# STEP6.net
KiCad netlist of a schematic drawn in EAGLE
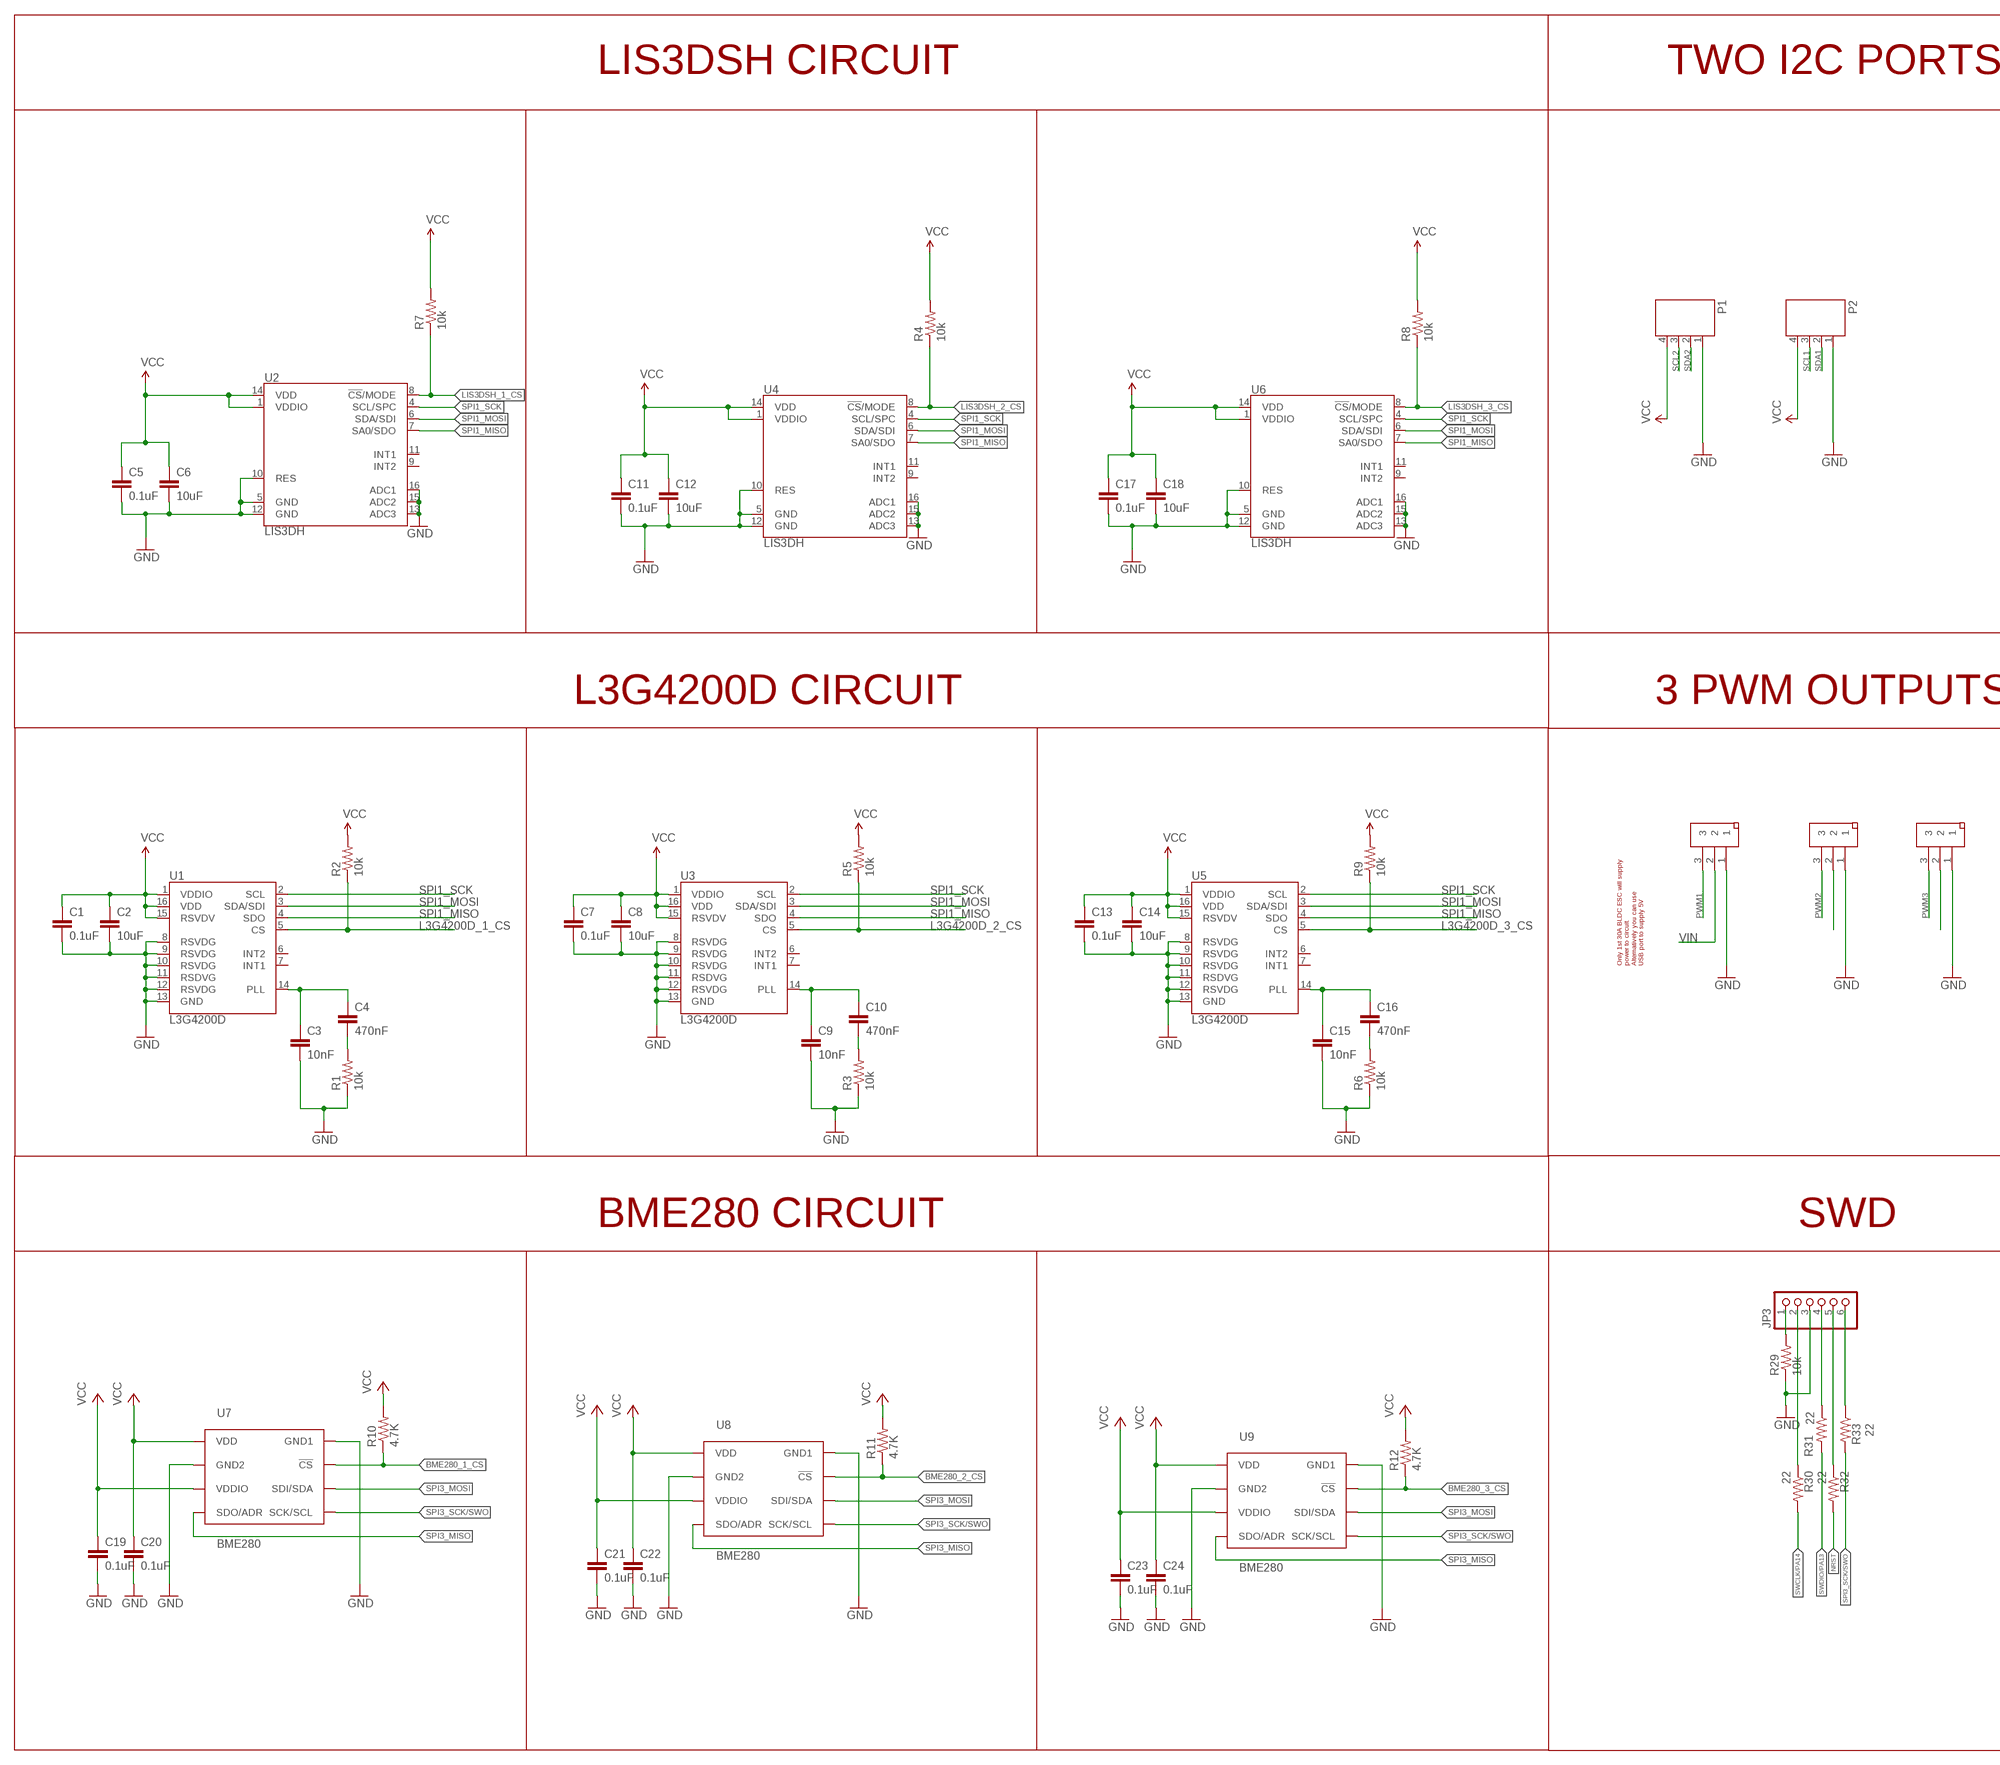
[diagram p0: schematic, sheet 1, part 1 of 2]
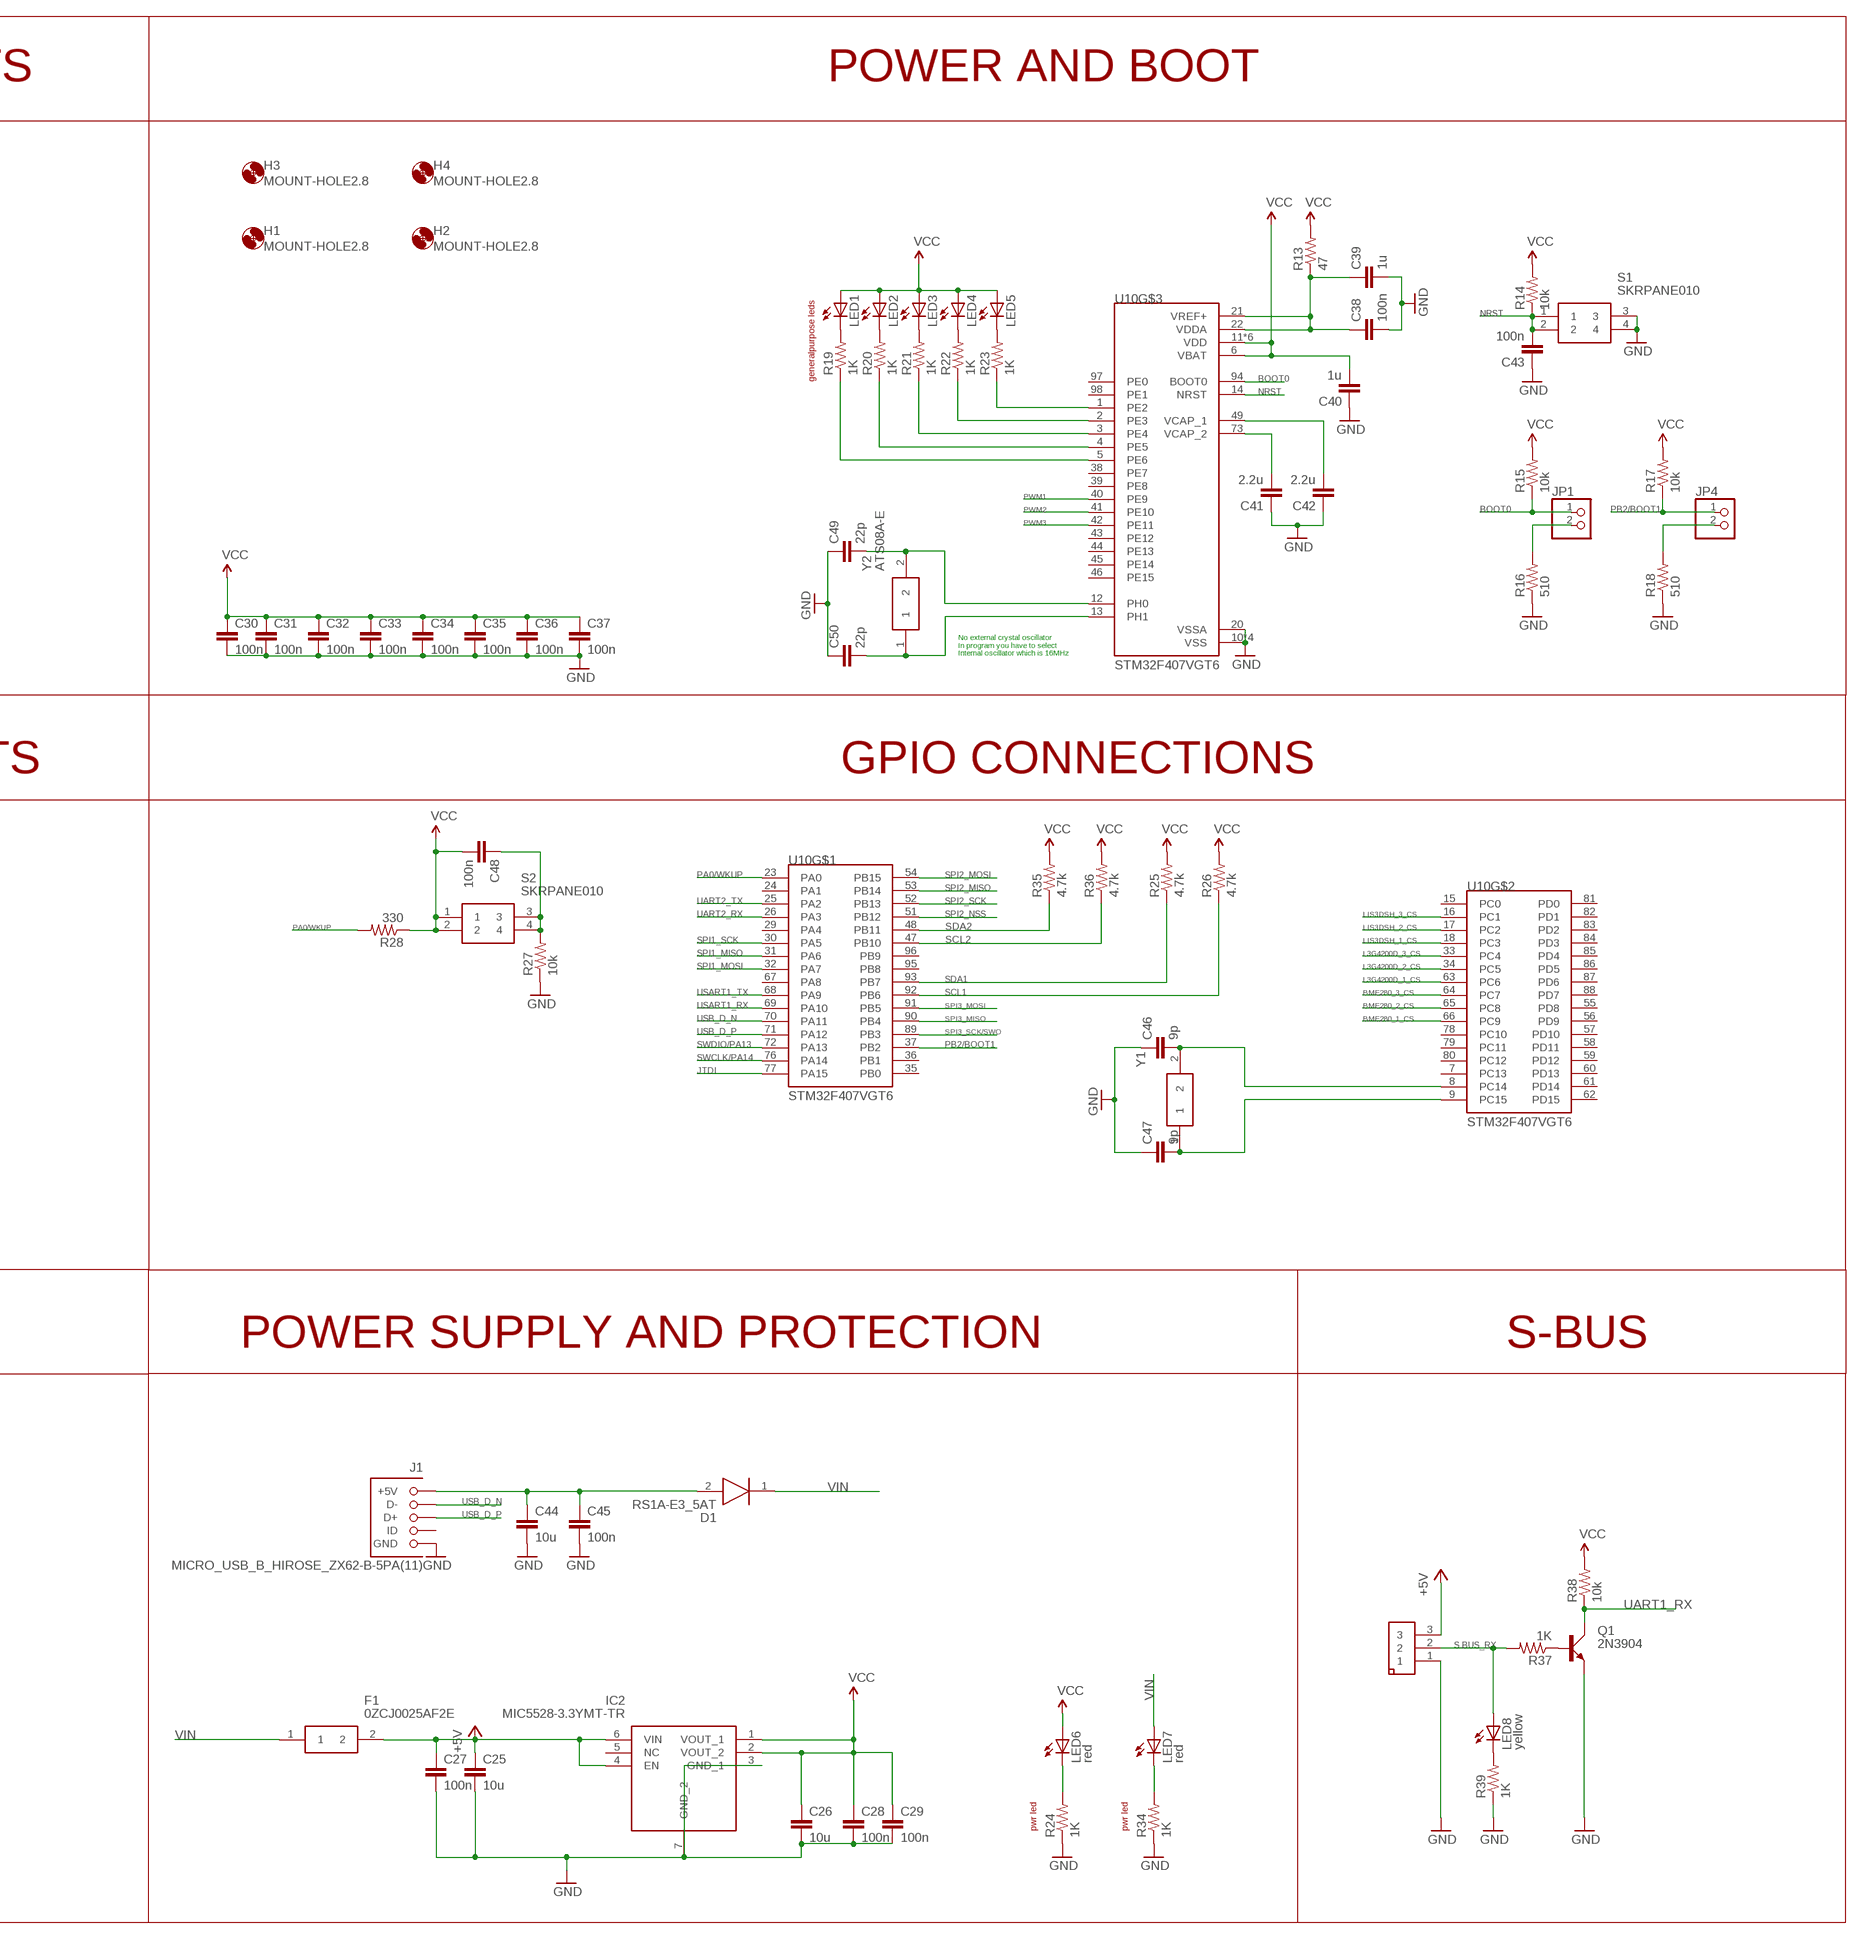
[diagram p1: schematic, sheet 1, part 2 of 2]

(export (version "E")
  (design (tool "Eeschema 10.0.6"))
  (components
    (comp (ref "C1")
      (value "0.1uF")
      (footprint "eagle-import:0402-CAP")
      (libsource (lib "eagle-import") (part "CAP0402-CAP"))
    )
    (comp (ref "C2")
      (value "10uF")
      (footprint "eagle-import:1206")
      (libsource (lib "eagle-import") (part "CAP1206"))
    )
    (comp (ref "C3")
      (value "10nF")
      (footprint "eagle-import:0402-CAP")
      (libsource (lib "eagle-import") (part "CAP0402-CAP"))
    )
    (comp (ref "C4")
      (value "470nF")
      (footprint "eagle-import:0402-CAP")
      (libsource (lib "eagle-import") (part "CAP0402-CAP"))
    )
    (comp (ref "C5")
      (value "0.1uF")
      (footprint "eagle-import:0402")
      (libsource (lib "eagle-import") (part "0.1UF-0402-16V-10%"))
    )
    (comp (ref "C6")
      (value "10uF")
      (footprint "eagle-import:0603")
      (libsource (lib "eagle-import") (part "10UF-0603-6.3V-20%"))
    )
    (comp (ref "C7")
      (value "0.1uF")
      (footprint "eagle-import:0402-CAP")
      (libsource (lib "eagle-import") (part "CAP0402-CAP"))
    )
    (comp (ref "C8")
      (value "10uF")
      (footprint "eagle-import:1206")
      (libsource (lib "eagle-import") (part "CAP1206"))
    )
    (comp (ref "C9")
      (value "10nF")
      (footprint "eagle-import:0402-CAP")
      (libsource (lib "eagle-import") (part "CAP0402-CAP"))
    )
    (comp (ref "C10")
      (value "470nF")
      (footprint "eagle-import:0402-CAP")
      (libsource (lib "eagle-import") (part "CAP0402-CAP"))
    )
    (comp (ref "C11")
      (value "0.1uF")
      (footprint "eagle-import:0402")
      (libsource (lib "eagle-import") (part "0.1UF-0402-16V-10%"))
    )
    (comp (ref "C12")
      (value "10uF")
      (footprint "eagle-import:0603")
      (libsource (lib "eagle-import") (part "10UF-0603-6.3V-20%"))
    )
    (comp (ref "C13")
      (value "0.1uF")
      (footprint "eagle-import:0402-CAP")
      (libsource (lib "eagle-import") (part "CAP0402-CAP"))
    )
    (comp (ref "C14")
      (value "10uF")
      (footprint "eagle-import:1206")
      (libsource (lib "eagle-import") (part "CAP1206"))
    )
    (comp (ref "C15")
      (value "10nF")
      (footprint "eagle-import:0402-CAP")
      (libsource (lib "eagle-import") (part "CAP0402-CAP"))
    )
    (comp (ref "C16")
      (value "470nF")
      (footprint "eagle-import:0402-CAP")
      (libsource (lib "eagle-import") (part "CAP0402-CAP"))
    )
    (comp (ref "C17")
      (value "0.1uF")
      (footprint "eagle-import:0402")
      (libsource (lib "eagle-import") (part "0.1UF-0402-16V-10%"))
    )
    (comp (ref "C18")
      (value "10uF")
      (footprint "eagle-import:0603")
      (libsource (lib "eagle-import") (part "10UF-0603-6.3V-20%"))
    )
    (comp (ref "C19")
      (value "0.1uF")
      (footprint "eagle-import:0603-CAP")
      (libsource (lib "eagle-import") (part "0.1UF-25V-5%(0603)"))
    )
    (comp (ref "C20")
      (value "0.1uF")
      (footprint "eagle-import:0603-CAP")
      (libsource (lib "eagle-import") (part "0.1UF-25V-5%(0603)"))
    )
    (comp (ref "C21")
      (value "0.1uF")
      (footprint "eagle-import:0603-CAP")
      (libsource (lib "eagle-import") (part "0.1UF-25V-5%(0603)"))
    )
    (comp (ref "C22")
      (value "0.1uF")
      (footprint "eagle-import:0603-CAP")
      (libsource (lib "eagle-import") (part "0.1UF-25V-5%(0603)"))
    )
    (comp (ref "C23")
      (value "0.1uF")
      (footprint "eagle-import:0603-CAP")
      (libsource (lib "eagle-import") (part "0.1UF-25V-5%(0603)"))
    )
    (comp (ref "C24")
      (value "0.1uF")
      (footprint "eagle-import:0603-CAP")
      (libsource (lib "eagle-import") (part "0.1UF-25V-5%(0603)"))
    )
    (comp (ref "C25")
      (value "10u")
      (footprint "eagle-import:C0805")
      (libsource (lib "eagle-import") (part "C-EUC0805"))
    )
    (comp (ref "C26")
      (value "10u")
      (footprint "eagle-import:C0805")
      (libsource (lib "eagle-import") (part "C-EUC0805"))
    )
    (comp (ref "C27")
      (value "100n")
      (footprint "eagle-import:C0402")
      (libsource (lib "eagle-import") (part "C-EUC0402"))
    )
    (comp (ref "C28")
      (value "100n")
      (footprint "eagle-import:C0402")
      (libsource (lib "eagle-import") (part "C-EUC0402"))
    )
    (comp (ref "C29")
      (value "100n")
      (footprint "eagle-import:C0402")
      (libsource (lib "eagle-import") (part "C-EUC0402"))
    )
    (comp (ref "C30")
      (value "100n")
      (footprint "eagle-import:C0402")
      (libsource (lib "eagle-import") (part "C-EUC0402"))
    )
    (comp (ref "C31")
      (value "100n")
      (footprint "eagle-import:C0402")
      (libsource (lib "eagle-import") (part "C-EUC0402"))
    )
    (comp (ref "C32")
      (value "100n")
      (footprint "eagle-import:C0402")
      (libsource (lib "eagle-import") (part "C-EUC0402"))
    )
    (comp (ref "C33")
      (value "100n")
      (footprint "eagle-import:C0402")
      (libsource (lib "eagle-import") (part "C-EUC0402"))
    )
    (comp (ref "C34")
      (value "100n")
      (footprint "eagle-import:C0402")
      (libsource (lib "eagle-import") (part "C-EUC0402"))
    )
    (comp (ref "C35")
      (value "100n")
      (footprint "eagle-import:C0402")
      (libsource (lib "eagle-import") (part "C-EUC0402"))
    )
    (comp (ref "C36")
      (value "100n")
      (footprint "eagle-import:C0402")
      (libsource (lib "eagle-import") (part "C-EUC0402"))
    )
    (comp (ref "C37")
      (value "100n")
      (footprint "eagle-import:C0402")
      (libsource (lib "eagle-import") (part "C-EUC0402"))
    )
    (comp (ref "C38")
      (value "100n")
      (footprint "eagle-import:C0402")
      (libsource (lib "eagle-import") (part "C-EUC0402"))
    )
    (comp (ref "C39")
      (value "1u")
      (footprint "eagle-import:C0402")
      (libsource (lib "eagle-import") (part "C-EUC0402"))
    )
    (comp (ref "C40")
      (value "1u")
      (footprint "eagle-import:C0402")
      (libsource (lib "eagle-import") (part "C-EUC0402"))
    )
    (comp (ref "C41")
      (value "2.2u")
      (footprint "eagle-import:C0603")
      (libsource (lib "eagle-import") (part "C-EUC0603"))
    )
    (comp (ref "C42")
      (value "2.2u")
      (footprint "eagle-import:C0603")
      (libsource (lib "eagle-import") (part "C-EUC0603"))
    )
    (comp (ref "C43")
      (value "100n")
      (footprint "eagle-import:C0402")
      (libsource (lib "eagle-import") (part "C-EUC0402"))
    )
    (comp (ref "C44")
      (value "10u")
      (footprint "eagle-import:C0805")
      (libsource (lib "eagle-import") (part "C-EUC0805"))
    )
    (comp (ref "C45")
      (value "100n")
      (footprint "eagle-import:C0402")
      (libsource (lib "eagle-import") (part "C-EUC0402"))
    )
    (comp (ref "C46")
      (value "9p")
      (footprint "eagle-import:C0402")
      (libsource (lib "eagle-import") (part "C-EUC0402"))
    )
    (comp (ref "C47")
      (value "9p")
      (footprint "eagle-import:C0402")
      (libsource (lib "eagle-import") (part "C-EUC0402"))
    )
    (comp (ref "C48")
      (value "100n")
      (footprint "eagle-import:C0402")
      (libsource (lib "eagle-import") (part "C-EUC0402"))
    )
    (comp (ref "C49")
      (value "22p")
      (footprint "eagle-import:C0402")
      (libsource (lib "eagle-import") (part "C-EUC0402"))
    )
    (comp (ref "C50")
      (value "22p")
      (footprint "eagle-import:C0402")
      (libsource (lib "eagle-import") (part "C-EUC0402"))
    )
    (comp (ref "D1")
      (value "RS1A-E3_5AT")
      (footprint "eagle-import:DIOM5127X229N")
      (fields
        (field (name "MANUFACTURER_PART_NUMBER") "RS1A-E3/5AT")
        (field (name "MOUSER_PART_NUMBER") "625-RS1A-E3/5AT")
      )
      (libsource (lib "eagle-import") (part "RS1A-E3_5AT"))
    )
    (comp (ref "F1")
      (value "0ZCJ0025AF2E")
      (footprint "eagle-import:FUSC3216X75N")
      (libsource (lib "eagle-import") (part "0ZCJ0025AF2E"))
    )
    (comp (ref "H1")
      (value "MOUNT-HOLE2.8")
      (footprint "eagle-import:2,8")
      (libsource (lib "eagle-import") (part "MOUNT-HOLE2.8"))
    )
    (comp (ref "H2")
      (value "MOUNT-HOLE2.8")
      (footprint "eagle-import:2,8")
      (libsource (lib "eagle-import") (part "MOUNT-HOLE2.8"))
    )
    (comp (ref "H3")
      (value "MOUNT-HOLE2.8")
      (footprint "eagle-import:2,8")
      (libsource (lib "eagle-import") (part "MOUNT-HOLE2.8"))
    )
    (comp (ref "H4")
      (value "MOUNT-HOLE2.8")
      (footprint "eagle-import:2,8")
      (libsource (lib "eagle-import") (part "MOUNT-HOLE2.8"))
    )
    (comp (ref "IC2")
      (value "MIC5528-3.3YMT-TR")
      (footprint "eagle-import:SON40P120X120X60-7N")
      (fields
        (field (name "MOUSER_PART_NUMBER") "998-MIC5528-3.3YMTTR")
        (field (name "RS_PART_NUMBER") "1773292P")
      )
      (libsource (lib "eagle-import") (part "MIC5528-3.3YMT-TR"))
    )
    (comp (ref "J1")
      (value "MICRO_USB_B_HIROSE_ZX62-B-5PA(11)")
      (footprint "eagle-import:USB_MICRO_B-HIROSE-ZX62-B-5PA(11)")
      (libsource (lib "eagle-import") (part "MICRO_USB_B_HIROSE_ZX62-B-5PA(11)"))
    )
    (comp (ref "JP1")
      (value "PINHD-1X2")
      (footprint "eagle-import:1X02")
      (libsource (lib "eagle-import") (part "PINHD-1X2"))
    )
    (comp (ref "JP3")
      (value "PINHD-1X6")
      (footprint "eagle-import:1X06")
      (libsource (lib "eagle-import") (part "PINHD-1X6"))
    )
    (comp (ref "JP4")
      (value "PINHD-1X2")
      (footprint "eagle-import:1X02")
      (libsource (lib "eagle-import") (part "PINHD-1X2"))
    )
    (comp (ref "LED1")
      (value "LEDCHIP-LED0603")
      (footprint "eagle-import:CHIP-LED0603")
      (libsource (lib "eagle-import") (part "LEDCHIP-LED0603"))
    )
    (comp (ref "LED2")
      (value "LEDCHIP-LED0603")
      (footprint "eagle-import:CHIP-LED0603")
      (libsource (lib "eagle-import") (part "LEDCHIP-LED0603"))
    )
    (comp (ref "LED3")
      (value "LEDCHIP-LED0603")
      (footprint "eagle-import:CHIP-LED0603")
      (libsource (lib "eagle-import") (part "LEDCHIP-LED0603"))
    )
    (comp (ref "LED4")
      (value "LEDCHIP-LED0603")
      (footprint "eagle-import:CHIP-LED0603")
      (libsource (lib "eagle-import") (part "LEDCHIP-LED0603"))
    )
    (comp (ref "LED5")
      (value "LEDCHIP-LED0603")
      (footprint "eagle-import:CHIP-LED0603")
      (libsource (lib "eagle-import") (part "LEDCHIP-LED0603"))
    )
    (comp (ref "LED6")
      (value "red")
      (footprint "eagle-import:CHIP-LED0603")
      (libsource (lib "eagle-import") (part "LEDCHIP-LED0603"))
    )
    (comp (ref "LED7")
      (value "red")
      (footprint "eagle-import:CHIP-LED0603")
      (libsource (lib "eagle-import") (part "LEDCHIP-LED0603"))
    )
    (comp (ref "LED8")
      (value "yellow")
      (footprint "eagle-import:CHIP-LED0603")
      (libsource (lib "eagle-import") (part "LEDCHIP-LED0603"))
    )
    (comp (ref "P1")
      (value "JST-PH4")
      (footprint "eagle-import:JST-PH4")
      (libsource (lib "eagle-import") (part "JST-PH4"))
    )
    (comp (ref "P2")
      (value "JST-PH4")
      (footprint "eagle-import:JST-PH4")
      (libsource (lib "eagle-import") (part "JST-PH4"))
    )
    (comp (ref "Q1")
      (value "2N3904")
      (footprint "eagle-import:SOT23")
      (libsource (lib "eagle-import") (part "2N3904"))
    )
    (comp (ref "R1")
      (value "10k")
      (footprint "eagle-import:0402-RES")
      (libsource (lib "eagle-import") (part "RESISTOR0402-RES"))
    )
    (comp (ref "R2")
      (value "10k")
      (footprint "eagle-import:0402-RES")
      (libsource (lib "eagle-import") (part "RESISTOR0402-RES"))
    )
    (comp (ref "R3")
      (value "10k")
      (footprint "eagle-import:0402-RES")
      (libsource (lib "eagle-import") (part "RESISTOR0402-RES"))
    )
    (comp (ref "R4")
      (value "10k")
      (footprint "eagle-import:R0402")
      (libsource (lib "eagle-import") (part "R-US_R0402"))
    )
    (comp (ref "R5")
      (value "10k")
      (footprint "eagle-import:0402-RES")
      (libsource (lib "eagle-import") (part "RESISTOR0402-RES"))
    )
    (comp (ref "R6")
      (value "10k")
      (footprint "eagle-import:0402-RES")
      (libsource (lib "eagle-import") (part "RESISTOR0402-RES"))
    )
    (comp (ref "R7")
      (value "10k")
      (footprint "eagle-import:R0402")
      (libsource (lib "eagle-import") (part "R-US_R0402"))
    )
    (comp (ref "R8")
      (value "10k")
      (footprint "eagle-import:R0402")
      (libsource (lib "eagle-import") (part "R-US_R0402"))
    )
    (comp (ref "R9")
      (value "10k")
      (footprint "eagle-import:0402-RES")
      (libsource (lib "eagle-import") (part "RESISTOR0402-RES"))
    )
    (comp (ref "R10")
      (value "4.7K")
      (footprint "eagle-import:R0402")
      (libsource (lib "eagle-import") (part "R-US_R0402"))
    )
    (comp (ref "R11")
      (value "4.7K")
      (footprint "eagle-import:R0402")
      (libsource (lib "eagle-import") (part "R-US_R0402"))
    )
    (comp (ref "R12")
      (value "4.7K")
      (footprint "eagle-import:R0402")
      (libsource (lib "eagle-import") (part "R-US_R0402"))
    )
    (comp (ref "R13")
      (value "47")
      (footprint "eagle-import:R1206")
      (libsource (lib "eagle-import") (part "R-US_R1206"))
    )
    (comp (ref "R14")
      (value "10k")
      (footprint "eagle-import:R0402")
      (libsource (lib "eagle-import") (part "R-US_R0402"))
    )
    (comp (ref "R15")
      (value "10k")
      (footprint "eagle-import:R0402")
      (libsource (lib "eagle-import") (part "R-US_R0402"))
    )
    (comp (ref "R16")
      (value "510")
      (footprint "eagle-import:R0402")
      (libsource (lib "eagle-import") (part "R-US_R0402"))
    )
    (comp (ref "R17")
      (value "10k")
      (footprint "eagle-import:R0402")
      (libsource (lib "eagle-import") (part "R-US_R0402"))
    )
    (comp (ref "R18")
      (value "510")
      (footprint "eagle-import:R0402")
      (libsource (lib "eagle-import") (part "R-US_R0402"))
    )
    (comp (ref "R19")
      (value "1K")
      (footprint "eagle-import:R0402")
      (libsource (lib "eagle-import") (part "R-US_R0402"))
    )
    (comp (ref "R20")
      (value "1K")
      (footprint "eagle-import:R0402")
      (libsource (lib "eagle-import") (part "R-US_R0402"))
    )
    (comp (ref "R21")
      (value "1K")
      (footprint "eagle-import:R0402")
      (libsource (lib "eagle-import") (part "R-US_R0402"))
    )
    (comp (ref "R22")
      (value "1K")
      (footprint "eagle-import:R0402")
      (libsource (lib "eagle-import") (part "R-US_R0402"))
    )
    (comp (ref "R23")
      (value "1K")
      (footprint "eagle-import:R0402")
      (libsource (lib "eagle-import") (part "R-US_R0402"))
    )
    (comp (ref "R24")
      (value "1K")
      (footprint "eagle-import:R0402")
      (libsource (lib "eagle-import") (part "R-US_R0402"))
    )
    (comp (ref "R25")
      (value "4.7k")
      (footprint "eagle-import:R0402")
      (libsource (lib "eagle-import") (part "R-US_R0402"))
    )
    (comp (ref "R26")
      (value "4.7k")
      (footprint "eagle-import:R0402")
      (libsource (lib "eagle-import") (part "R-US_R0402"))
    )
    (comp (ref "R27")
      (value "10k")
      (footprint "eagle-import:R0402")
      (libsource (lib "eagle-import") (part "R-US_R0402"))
    )
    (comp (ref "R28")
      (value "330")
      (footprint "eagle-import:R0402")
      (libsource (lib "eagle-import") (part "R-US_R0402"))
    )
    (comp (ref "R29")
      (value "10k")
      (footprint "eagle-import:0402-RES")
      (libsource (lib "eagle-import") (part "RESISTOR0402-RES"))
    )
    (comp (ref "R30")
      (value "22")
      (footprint "eagle-import:0402-RES")
      (libsource (lib "eagle-import") (part "RESISTOR0402-RES"))
    )
    (comp (ref "R31")
      (value "22")
      (footprint "eagle-import:0402-RES")
      (libsource (lib "eagle-import") (part "RESISTOR0402-RES"))
    )
    (comp (ref "R32")
      (value "22")
      (footprint "eagle-import:0402-RES")
      (libsource (lib "eagle-import") (part "RESISTOR0402-RES"))
    )
    (comp (ref "R33")
      (value "22")
      (footprint "eagle-import:0402-RES")
      (libsource (lib "eagle-import") (part "RESISTOR0402-RES"))
    )
    (comp (ref "R34")
      (value "1K")
      (footprint "eagle-import:R0402")
      (libsource (lib "eagle-import") (part "R-US_R0402"))
    )
    (comp (ref "R35")
      (value "4.7k")
      (footprint "eagle-import:R0402")
      (libsource (lib "eagle-import") (part "R-US_R0402"))
    )
    (comp (ref "R36")
      (value "4.7k")
      (footprint "eagle-import:R0402")
      (libsource (lib "eagle-import") (part "R-US_R0402"))
    )
    (comp (ref "R37")
      (value "1K")
      (footprint "eagle-import:R0402")
      (libsource (lib "eagle-import") (part "R-US_R0402"))
    )
    (comp (ref "R38")
      (value "10k")
      (footprint "eagle-import:R0402")
      (libsource (lib "eagle-import") (part "R-US_R0402"))
    )
    (comp (ref "R39")
      (value "1K")
      (footprint "eagle-import:R0402")
      (libsource (lib "eagle-import") (part "R-US_R0402"))
    )
    (comp (ref "S1")
      (value "SKRPANE010")
      (footprint "eagle-import:SKRPADE010")
      (fields (field (name "MOUSER_PART_NUMBER") "688-SKRPANE010"))
      (libsource (lib "eagle-import") (part "SKRPANE010"))
    )
    (comp (ref "S2")
      (value "SKRPANE010")
      (footprint "eagle-import:SKRPADE010")
      (fields (field (name "MOUSER_PART_NUMBER") "688-SKRPANE010"))
      (libsource (lib "eagle-import") (part "SKRPANE010"))
    )
    (comp (ref "U$1")
      (value "JST-PH3")
      (footprint "eagle-import:JST-PH3")
      (libsource (lib "eagle-import") (part "JST-PH3"))
    )
    (comp (ref "U$2")
      (value "JST-PH3")
      (footprint "eagle-import:JST-PH3")
      (libsource (lib "eagle-import") (part "JST-PH3"))
    )
    (comp (ref "U$3")
      (value "JST-PH3")
      (footprint "eagle-import:JST-PH3")
      (libsource (lib "eagle-import") (part "JST-PH3"))
    )
    (comp (ref "U$4")
      (value "JST-PH3")
      (footprint "eagle-import:JST-PH3")
      (libsource (lib "eagle-import") (part "JST-PH3"))
    )
    (comp (ref "U1")
      (value "L3G4200D")
      (footprint "eagle-import:LGA16-4X4")
      (libsource (lib "eagle-import") (part "L3G4200D"))
    )
    (comp (ref "U2")
      (value "LIS3DH")
      (footprint "eagle-import:LGA-16-3X3")
      (libsource (lib "eagle-import") (part "LIS3DH"))
    )
    (comp (ref "U3")
      (value "L3G4200D")
      (footprint "eagle-import:LGA16-4X4")
      (libsource (lib "eagle-import") (part "L3G4200D"))
    )
    (comp (ref "U4")
      (value "LIS3DH")
      (footprint "eagle-import:LGA-16-3X3")
      (libsource (lib "eagle-import") (part "LIS3DH"))
    )
    (comp (ref "U5")
      (value "L3G4200D")
      (footprint "eagle-import:LGA16-4X4")
      (libsource (lib "eagle-import") (part "L3G4200D"))
    )
    (comp (ref "U6")
      (value "LIS3DH")
      (footprint "eagle-import:LGA-16-3X3")
      (libsource (lib "eagle-import") (part "LIS3DH"))
    )
    (comp (ref "U7")
      (value "BME280")
      (footprint "eagle-import:BME280_LGA")
      (libsource (lib "eagle-import") (part "BME280"))
    )
    (comp (ref "U8")
      (value "BME280")
      (footprint "eagle-import:BME280_LGA")
      (libsource (lib "eagle-import") (part "BME280"))
    )
    (comp (ref "U9")
      (value "BME280")
      (footprint "eagle-import:BME280_LGA")
      (libsource (lib "eagle-import") (part "BME280"))
    )
    (comp (ref "U10")
      (value "STM32F407VGT6")
      (footprint "eagle-import:QFP50P1600X1600X160-100N")
      (fields (field (name "MF") "STMicroelectronics"))
      (libsource (lib "eagle-import") (part "STM32F407VGT6"))
    )
    (comp (ref "Y1")
      (value "CM7V-T1A-32.768K-9PF-20PPM-TA-")
      (footprint "eagle-import:CM7VT1A32768KHZ125PF10PPMTBQC")
      (fields
        (field (name "MANUFACTURER_PART_NUMBER") "CM7V-T1A-32.768k-9pF-20PPM-TA-QA T3")
        (field (name "MOUSER_PART_NUMBER") "428-201568-MG03")
      )
      (libsource (lib "eagle-import") (part "CM7V-T1A-32.768K-9PF-20PPM-TA-"))
    )
    (comp (ref "Y2")
      (value "ATS08A-E")
      (footprint "eagle-import:ATS041C-E")
      (fields (field (name "MOUSER_PART_NUMBER") "774-ATS08A-E"))
      (libsource (lib "eagle-import") (part "ATS08A-E"))
    )
  )
  (nets
    (net (code "1") (name "+5V") (class "Default")
      (node (ref "C25") (pin "1") (pinfunction "1_1") (pintype "passive"))
      (node (ref "C27") (pin "1") (pinfunction "1_1") (pintype "passive"))
      (node (ref "F1") (pin "2") (pinfunction "2_2") (pintype "bidirectional"))
      (node (ref "IC2") (pin "4") (pinfunction "EN_4") (pintype "bidirectional"))
      (node (ref "IC2") (pin "6") (pinfunction "VIN_6") (pintype "bidirectional"))
      (node (ref "U$4") (pin "3") (pinfunction "3_3") (pintype "bidirectional"))
    )
    (net (code "2") (name "/BOOT0") (class "Default")
      (node (ref "JP1") (pin "1") (pinfunction "1_1") (pintype "passive"))
      (node (ref "R15") (pin "1") (pinfunction "1_1") (pintype "passive"))
      (node (ref "U10") (pin "94") (pinfunction "BOOT0_94") (pintype "input"))
    )
    (net (code "3") (name "/JTDI") (class "Default")
      (node (ref "U10") (pin "77") (pinfunction "PA15_77") (pintype "bidirectional"))
    )
    (net (code "4") (name "/L3G4200D_1_CS") (class "Default")
      (node (ref "R2") (pin "1") (pinfunction "1_1") (pintype "passive"))
      (node (ref "U1") (pin "5") (pinfunction "CS_5") (pintype "bidirectional"))
      (node (ref "U10") (pin "63") (pinfunction "PC6_63") (pintype "bidirectional"))
    )
    (net (code "5") (name "/L3G4200D_2_CS") (class "Default")
      (node (ref "R5") (pin "1") (pinfunction "1_1") (pintype "passive"))
      (node (ref "U10") (pin "34") (pinfunction "PC5_34") (pintype "bidirectional"))
      (node (ref "U3") (pin "5") (pinfunction "CS_5") (pintype "bidirectional"))
    )
    (net (code "6") (name "/L3G4200D_3_CS") (class "Default")
      (node (ref "R9") (pin "1") (pinfunction "1_1") (pintype "passive"))
      (node (ref "U10") (pin "33") (pinfunction "PC4_33") (pintype "bidirectional"))
      (node (ref "U5") (pin "5") (pinfunction "CS_5") (pintype "bidirectional"))
    )
    (net (code "7") (name "/PA0{slash}WKUP") (class "Default")
      (node (ref "R28") (pin "2") (pinfunction "2_2") (pintype "passive"))
      (node (ref "U10") (pin "23") (pinfunction "PA0_23") (pintype "bidirectional"))
    )
    (net (code "8") (name "/PB2{slash}BOOT1") (class "Default")
      (node (ref "JP4") (pin "1") (pinfunction "1_1") (pintype "passive"))
      (node (ref "R17") (pin "1") (pinfunction "1_1") (pintype "passive"))
      (node (ref "U10") (pin "37") (pinfunction "PB2_37") (pintype "bidirectional"))
    )
    (net (code "9") (name "/PWM1") (class "Default")
      (node (ref "U$1") (pin "3") (pinfunction "3_3") (pintype "bidirectional"))
      (node (ref "U10") (pin "40") (pinfunction "PE9_40") (pintype "bidirectional"))
    )
    (net (code "10") (name "/PWM2") (class "Default")
      (node (ref "U$2") (pin "3") (pinfunction "3_3") (pintype "bidirectional"))
      (node (ref "U10") (pin "41") (pinfunction "PE10_41") (pintype "bidirectional"))
    )
    (net (code "11") (name "/PWM3") (class "Default")
      (node (ref "U$3") (pin "3") (pinfunction "3_3") (pintype "bidirectional"))
      (node (ref "U10") (pin "42") (pinfunction "PE11_42") (pintype "bidirectional"))
    )
    (net (code "12") (name "/S.BUS_RX") (class "Default")
      (node (ref "LED8") (pin "A") (pinfunction "A_A") (pintype "passive"))
      (node (ref "R37") (pin "2") (pinfunction "2_2") (pintype "passive"))
      (node (ref "U$4") (pin "2") (pinfunction "2_2") (pintype "bidirectional"))
    )
    (net (code "13") (name "/SCL1") (class "Default")
      (node (ref "P2") (pin "3") (pinfunction "3_3") (pintype "passive"))
      (node (ref "R26") (pin "1") (pinfunction "1_1") (pintype "passive"))
      (node (ref "U10") (pin "92") (pinfunction "PB6_92") (pintype "bidirectional"))
    )
    (net (code "14") (name "/SCL2") (class "Default")
      (node (ref "P1") (pin "3") (pinfunction "3_3") (pintype "passive"))
      (node (ref "R36") (pin "1") (pinfunction "1_1") (pintype "passive"))
      (node (ref "U10") (pin "47") (pinfunction "PB10_47") (pintype "bidirectional"))
    )
    (net (code "15") (name "/SDA1") (class "Default")
      (node (ref "P2") (pin "2") (pinfunction "2_2") (pintype "passive"))
      (node (ref "R25") (pin "1") (pinfunction "1_1") (pintype "passive"))
      (node (ref "U10") (pin "93") (pinfunction "PB7_93") (pintype "bidirectional"))
    )
    (net (code "16") (name "/SDA2") (class "Default")
      (node (ref "P1") (pin "2") (pinfunction "2_2") (pintype "passive"))
      (node (ref "R35") (pin "1") (pinfunction "1_1") (pintype "passive"))
      (node (ref "U10") (pin "48") (pinfunction "PB11_48") (pintype "bidirectional"))
    )
    (net (code "17") (name "/SPI2_MISO") (class "Default")
      (node (ref "U10") (pin "53") (pinfunction "PB14_53") (pintype "bidirectional"))
    )
    (net (code "18") (name "/SPI2_MOSI") (class "Default")
      (node (ref "U10") (pin "54") (pinfunction "PB15_54") (pintype "bidirectional"))
    )
    (net (code "19") (name "/SPI2_NSS") (class "Default")
      (node (ref "U10") (pin "51") (pinfunction "PB12_51") (pintype "bidirectional"))
    )
    (net (code "20") (name "/SPI2_SCK") (class "Default")
      (node (ref "U10") (pin "52") (pinfunction "PB13_52") (pintype "bidirectional"))
    )
    (net (code "21") (name "/UART1_RX") (class "Default")
      (node (ref "Q1") (pin "3") (pinfunction "C_3") (pintype "passive"))
      (node (ref "R38") (pin "1") (pinfunction "1_1") (pintype "passive"))
    )
    (net (code "22") (name "/UART2_RX") (class "Default")
      (node (ref "U10") (pin "26") (pinfunction "PA3_26") (pintype "bidirectional"))
    )
    (net (code "23") (name "/UART2_TX") (class "Default")
      (node (ref "U10") (pin "25") (pinfunction "PA2_25") (pintype "bidirectional"))
    )
    (net (code "24") (name "/USART1_RX") (class "Default")
      (node (ref "U10") (pin "69") (pinfunction "PA10_69") (pintype "bidirectional"))
    )
    (net (code "25") (name "/USART1_TX") (class "Default")
      (node (ref "U10") (pin "68") (pinfunction "PA9_68") (pintype "bidirectional"))
    )
    (net (code "26") (name "/USB_D_N") (class "Default")
      (node (ref "J1") (pin "2") (pinfunction "D-_2") (pintype "bidirectional"))
      (node (ref "U10") (pin "70") (pinfunction "PA11_70") (pintype "bidirectional"))
    )
    (net (code "27") (name "/USB_D_P") (class "Default")
      (node (ref "J1") (pin "3") (pinfunction "D+_3") (pintype "bidirectional"))
      (node (ref "U10") (pin "71") (pinfunction "PA12_71") (pintype "bidirectional"))
    )
    (net (code "28") (name "/VIN") (class "Default")
      (node (ref "D1") (pin "1") (pinfunction "K_1") (pintype "bidirectional"))
      (node (ref "F1") (pin "1") (pinfunction "1_1") (pintype "bidirectional"))
      (node (ref "LED7") (pin "A") (pinfunction "A_A") (pintype "passive"))
      (node (ref "U$1") (pin "2") (pinfunction "2_2") (pintype "bidirectional"))
    )
    (net (code "29") (name "BME280_1_CS") (class "Default")
      (node (ref "R10") (pin "1") (pinfunction "1_1") (pintype "passive"))
      (node (ref "U10") (pin "66") (pinfunction "PC9_66") (pintype "bidirectional"))
      (node (ref "U7") (pin "P$2") (pinfunction "~{CS}_P$2") (pintype "bidirectional"))
    )
    (net (code "30") (name "BME280_2_CS") (class "Default")
      (node (ref "R11") (pin "1") (pinfunction "1_1") (pintype "passive"))
      (node (ref "U10") (pin "65") (pinfunction "PC8_65") (pintype "bidirectional"))
      (node (ref "U8") (pin "P$2") (pinfunction "~{CS}_P$2") (pintype "bidirectional"))
    )
    (net (code "31") (name "BME280_3_CS") (class "Default")
      (node (ref "R12") (pin "1") (pinfunction "1_1") (pintype "passive"))
      (node (ref "U10") (pin "64") (pinfunction "PC7_64") (pintype "bidirectional"))
      (node (ref "U9") (pin "P$2") (pinfunction "~{CS}_P$2") (pintype "bidirectional"))
    )
    (net (code "32") (name "GND") (class "Default")
      (node (ref "C1") (pin "2") (pinfunction "2_2") (pintype "passive"))
      (node (ref "C11") (pin "2") (pinfunction "2_2") (pintype "passive"))
      (node (ref "C12") (pin "2") (pinfunction "2_2") (pintype "passive"))
      (node (ref "C13") (pin "2") (pinfunction "2_2") (pintype "passive"))
      (node (ref "C14") (pin "2") (pinfunction "2_2") (pintype "passive"))
      (node (ref "C15") (pin "2") (pinfunction "2_2") (pintype "passive"))
      (node (ref "C17") (pin "2") (pinfunction "2_2") (pintype "passive"))
      (node (ref "C18") (pin "2") (pinfunction "2_2") (pintype "passive"))
      (node (ref "C19") (pin "2") (pinfunction "2_2") (pintype "passive"))
      (node (ref "C2") (pin "2") (pinfunction "2_2") (pintype "passive"))
      (node (ref "C20") (pin "2") (pinfunction "2_2") (pintype "passive"))
      (node (ref "C21") (pin "2") (pinfunction "2_2") (pintype "passive"))
      (node (ref "C22") (pin "2") (pinfunction "2_2") (pintype "passive"))
      (node (ref "C23") (pin "2") (pinfunction "2_2") (pintype "passive"))
      (node (ref "C24") (pin "2") (pinfunction "2_2") (pintype "passive"))
      (node (ref "C25") (pin "2") (pinfunction "2_2") (pintype "passive"))
      (node (ref "C26") (pin "2") (pinfunction "2_2") (pintype "passive"))
      (node (ref "C27") (pin "2") (pinfunction "2_2") (pintype "passive"))
      (node (ref "C28") (pin "2") (pinfunction "2_2") (pintype "passive"))
      (node (ref "C29") (pin "2") (pinfunction "2_2") (pintype "passive"))
      (node (ref "C3") (pin "2") (pinfunction "2_2") (pintype "passive"))
      (node (ref "C30") (pin "2") (pinfunction "2_2") (pintype "passive"))
      (node (ref "C31") (pin "2") (pinfunction "2_2") (pintype "passive"))
      (node (ref "C32") (pin "2") (pinfunction "2_2") (pintype "passive"))
      (node (ref "C33") (pin "2") (pinfunction "2_2") (pintype "passive"))
      (node (ref "C34") (pin "2") (pinfunction "2_2") (pintype "passive"))
      (node (ref "C35") (pin "2") (pinfunction "2_2") (pintype "passive"))
      (node (ref "C36") (pin "2") (pinfunction "2_2") (pintype "passive"))
      (node (ref "C37") (pin "2") (pinfunction "2_2") (pintype "passive"))
      (node (ref "C38") (pin "2") (pinfunction "2_2") (pintype "passive"))
      (node (ref "C39") (pin "2") (pinfunction "2_2") (pintype "passive"))
      (node (ref "C40") (pin "1") (pinfunction "1_1") (pintype "passive"))
      (node (ref "C41") (pin "1") (pinfunction "1_1") (pintype "passive"))
      (node (ref "C42") (pin "1") (pinfunction "1_1") (pintype "passive"))
      (node (ref "C43") (pin "1") (pinfunction "1_1") (pintype "passive"))
      (node (ref "C44") (pin "2") (pinfunction "2_2") (pintype "passive"))
      (node (ref "C45") (pin "2") (pinfunction "2_2") (pintype "passive"))
      (node (ref "C46") (pin "1") (pinfunction "1_1") (pintype "passive"))
      (node (ref "C47") (pin "1") (pinfunction "1_1") (pintype "passive"))
      (node (ref "C49") (pin "1") (pinfunction "1_1") (pintype "passive"))
      (node (ref "C5") (pin "2") (pinfunction "2_2") (pintype "passive"))
      (node (ref "C50") (pin "1") (pinfunction "1_1") (pintype "passive"))
      (node (ref "C6") (pin "2") (pinfunction "2_2") (pintype "passive"))
      (node (ref "C7") (pin "2") (pinfunction "2_2") (pintype "passive"))
      (node (ref "C8") (pin "2") (pinfunction "2_2") (pintype "passive"))
      (node (ref "C9") (pin "2") (pinfunction "2_2") (pintype "passive"))
      (node (ref "IC2") (pin "3") (pinfunction "GND_1_3") (pintype "bidirectional"))
      (node (ref "IC2") (pin "7") (pinfunction "GND_2_7") (pintype "bidirectional"))
      (node (ref "J1") (pin "5") (pinfunction "GND_5") (pintype "bidirectional"))
      (node (ref "JP3") (pin "3") (pinfunction "3_3") (pintype "passive"))
      (node (ref "P1") (pin "1") (pinfunction "1_1") (pintype "passive"))
      (node (ref "P2") (pin "1") (pinfunction "1_1") (pintype "passive"))
      (node (ref "Q1") (pin "2") (pinfunction "E_2") (pintype "passive"))
      (node (ref "R1") (pin "1") (pinfunction "1_1") (pintype "passive"))
      (node (ref "R16") (pin "1") (pinfunction "1_1") (pintype "passive"))
      (node (ref "R18") (pin "1") (pinfunction "1_1") (pintype "passive"))
      (node (ref "R24") (pin "1") (pinfunction "1_1") (pintype "passive"))
      (node (ref "R27") (pin "1") (pinfunction "1_1") (pintype "passive"))
      (node (ref "R29") (pin "1") (pinfunction "1_1") (pintype "passive"))
      (node (ref "R3") (pin "1") (pinfunction "1_1") (pintype "passive"))
      (node (ref "R34") (pin "1") (pinfunction "1_1") (pintype "passive"))
      (node (ref "R39") (pin "1") (pinfunction "1_1") (pintype "passive"))
      (node (ref "R6") (pin "1") (pinfunction "1_1") (pintype "passive"))
      (node (ref "S1") (pin "3") (pinfunction "3_3") (pintype "bidirectional"))
      (node (ref "S1") (pin "4") (pinfunction "4_4") (pintype "bidirectional"))
      (node (ref "U$1") (pin "1") (pinfunction "1_1") (pintype "bidirectional"))
      (node (ref "U$2") (pin "1") (pinfunction "1_1") (pintype "bidirectional"))
      (node (ref "U$3") (pin "1") (pinfunction "1_1") (pintype "bidirectional"))
      (node (ref "U$4") (pin "1") (pinfunction "1_1") (pintype "bidirectional"))
      (node (ref "U1") (pin "10") (pinfunction "RSVDG_10") (pintype "bidirectional"))
      (node (ref "U1") (pin "11") (pinfunction "RSDVG_11") (pintype "bidirectional"))
      (node (ref "U1") (pin "12") (pinfunction "RSVDG_12") (pintype "bidirectional"))
      (node (ref "U1") (pin "13") (pinfunction "GND_13") (pintype "bidirectional"))
      (node (ref "U1") (pin "8") (pinfunction "RSVDG_8") (pintype "bidirectional"))
      (node (ref "U1") (pin "9") (pinfunction "RSVDG_9") (pintype "bidirectional"))
      (node (ref "U10") (pin "10") (pinfunction "VSS_10") (pintype "power_in"))
      (node (ref "U10") (pin "20") (pinfunction "VSSA_20") (pintype "power_in"))
      (node (ref "U10") (pin "27") (pinfunction "VSS_27") (pintype "power_in"))
      (node (ref "U10") (pin "74") (pinfunction "VSS_74") (pintype "power_in"))
      (node (ref "U10") (pin "99") (pinfunction "VSS_99") (pintype "power_in"))
      (node (ref "U2") (pin "10") (pinfunction "RES_10") (pintype "bidirectional"))
      (node (ref "U2") (pin "12") (pinfunction "GND_12") (pintype "bidirectional"))
      (node (ref "U2") (pin "13") (pinfunction "ADC3_13") (pintype "bidirectional"))
      (node (ref "U2") (pin "15") (pinfunction "ADC2_15") (pintype "bidirectional"))
      (node (ref "U2") (pin "16") (pinfunction "ADC1_16") (pintype "bidirectional"))
      (node (ref "U2") (pin "5") (pinfunction "GND_5") (pintype "bidirectional"))
      (node (ref "U3") (pin "10") (pinfunction "RSVDG_10") (pintype "bidirectional"))
      (node (ref "U3") (pin "11") (pinfunction "RSDVG_11") (pintype "bidirectional"))
      (node (ref "U3") (pin "12") (pinfunction "RSVDG_12") (pintype "bidirectional"))
      (node (ref "U3") (pin "13") (pinfunction "GND_13") (pintype "bidirectional"))
      (node (ref "U3") (pin "8") (pinfunction "RSVDG_8") (pintype "bidirectional"))
      (node (ref "U3") (pin "9") (pinfunction "RSVDG_9") (pintype "bidirectional"))
      (node (ref "U4") (pin "10") (pinfunction "RES_10") (pintype "bidirectional"))
      (node (ref "U4") (pin "12") (pinfunction "GND_12") (pintype "bidirectional"))
      (node (ref "U4") (pin "13") (pinfunction "ADC3_13") (pintype "bidirectional"))
      (node (ref "U4") (pin "15") (pinfunction "ADC2_15") (pintype "bidirectional"))
      (node (ref "U4") (pin "16") (pinfunction "ADC1_16") (pintype "bidirectional"))
      (node (ref "U4") (pin "5") (pinfunction "GND_5") (pintype "bidirectional"))
      (node (ref "U5") (pin "10") (pinfunction "RSVDG_10") (pintype "bidirectional"))
      (node (ref "U5") (pin "11") (pinfunction "RSDVG_11") (pintype "bidirectional"))
      (node (ref "U5") (pin "12") (pinfunction "RSVDG_12") (pintype "bidirectional"))
      (node (ref "U5") (pin "13") (pinfunction "GND_13") (pintype "bidirectional"))
      (node (ref "U5") (pin "8") (pinfunction "RSVDG_8") (pintype "bidirectional"))
      (node (ref "U5") (pin "9") (pinfunction "RSVDG_9") (pintype "bidirectional"))
      (node (ref "U6") (pin "10") (pinfunction "RES_10") (pintype "bidirectional"))
      (node (ref "U6") (pin "12") (pinfunction "GND_12") (pintype "bidirectional"))
      (node (ref "U6") (pin "13") (pinfunction "ADC3_13") (pintype "bidirectional"))
      (node (ref "U6") (pin "15") (pinfunction "ADC2_15") (pintype "bidirectional"))
      (node (ref "U6") (pin "16") (pinfunction "ADC1_16") (pintype "bidirectional"))
      (node (ref "U6") (pin "5") (pinfunction "GND_5") (pintype "bidirectional"))
      (node (ref "U7") (pin "P$1") (pinfunction "GND1_P$1") (pintype "bidirectional"))
      (node (ref "U7") (pin "P$7") (pinfunction "GND2_P$7") (pintype "bidirectional"))
      (node (ref "U8") (pin "P$1") (pinfunction "GND1_P$1") (pintype "bidirectional"))
      (node (ref "U8") (pin "P$7") (pinfunction "GND2_P$7") (pintype "bidirectional"))
      (node (ref "U9") (pin "P$1") (pinfunction "GND1_P$1") (pintype "bidirectional"))
      (node (ref "U9") (pin "P$7") (pinfunction "GND2_P$7") (pintype "bidirectional"))
    )
    (net (code "33") (name "LIS3DSH_1_CS") (class "Default")
      (node (ref "R7") (pin "1") (pinfunction "1_1") (pintype "passive"))
      (node (ref "U10") (pin "18") (pinfunction "PC3_18") (pintype "bidirectional"))
      (node (ref "U2") (pin "8") (pinfunction "~{CS}/MODE_8") (pintype "bidirectional"))
    )
    (net (code "34") (name "LIS3DSH_2_CS") (class "Default")
      (node (ref "R4") (pin "1") (pinfunction "1_1") (pintype "passive"))
      (node (ref "U10") (pin "17") (pinfunction "PC2_17") (pintype "bidirectional"))
      (node (ref "U4") (pin "8") (pinfunction "~{CS}/MODE_8") (pintype "bidirectional"))
    )
    (net (code "35") (name "LIS3DSH_3_CS") (class "Default")
      (node (ref "R8") (pin "1") (pinfunction "1_1") (pintype "passive"))
      (node (ref "U10") (pin "16") (pinfunction "PC1_16") (pintype "bidirectional"))
      (node (ref "U6") (pin "8") (pinfunction "~{CS}/MODE_8") (pintype "bidirectional"))
    )
    (net (code "36") (name "NRST") (class "Default")
      (node (ref "C43") (pin "2") (pinfunction "2_2") (pintype "passive"))
      (node (ref "R14") (pin "1") (pinfunction "1_1") (pintype "passive"))
      (node (ref "R32") (pin "2") (pinfunction "2_2") (pintype "passive"))
      (node (ref "S1") (pin "1") (pinfunction "1_1") (pintype "bidirectional"))
      (node (ref "S1") (pin "2") (pinfunction "2_2") (pintype "bidirectional"))
      (node (ref "U10") (pin "14") (pinfunction "NRST_14") (pintype "bidirectional"))
    )
    (net (code "37") (name "Net-(C4-Pad2)") (class "Default")
      (node (ref "C4") (pin "2") (pinfunction "2_2") (pintype "passive"))
      (node (ref "R1") (pin "2") (pinfunction "2_2") (pintype "passive"))
    )
    (net (code "38") (name "Net-(C10-Pad2)") (class "Default")
      (node (ref "C10") (pin "2") (pinfunction "2_2") (pintype "passive"))
      (node (ref "R3") (pin "2") (pinfunction "2_2") (pintype "passive"))
    )
    (net (code "39") (name "Net-(C16-Pad2)") (class "Default")
      (node (ref "C16") (pin "2") (pinfunction "2_2") (pintype "passive"))
      (node (ref "R6") (pin "2") (pinfunction "2_2") (pintype "passive"))
    )
    (net (code "40") (name "Net-(C48-Pad1)") (class "Default")
      (node (ref "C48") (pin "1") (pinfunction "1_1") (pintype "passive"))
      (node (ref "R27") (pin "2") (pinfunction "2_2") (pintype "passive"))
      (node (ref "S2") (pin "3") (pinfunction "3_3") (pintype "bidirectional"))
      (node (ref "S2") (pin "4") (pinfunction "4_4") (pintype "bidirectional"))
    )
    (net (code "41") (name "Net-(D1-A)") (class "Default")
      (node (ref "C44") (pin "1") (pinfunction "1_1") (pintype "passive"))
      (node (ref "C45") (pin "1") (pinfunction "1_1") (pintype "passive"))
      (node (ref "D1") (pin "2") (pinfunction "A_2") (pintype "bidirectional"))
      (node (ref "J1") (pin "1") (pinfunction "+5V_1") (pintype "bidirectional"))
    )
    (net (code "42") (name "Net-(JP1-Pad2)") (class "Default")
      (node (ref "JP1") (pin "2") (pinfunction "2_2") (pintype "passive"))
      (node (ref "R16") (pin "2") (pinfunction "2_2") (pintype "passive"))
    )
    (net (code "43") (name "Net-(JP3-Pad1)") (class "Default")
      (node (ref "JP3") (pin "1") (pinfunction "1_1") (pintype "passive"))
      (node (ref "R29") (pin "2") (pinfunction "2_2") (pintype "passive"))
    )
    (net (code "44") (name "Net-(JP3-Pad2)") (class "Default")
      (node (ref "JP3") (pin "2") (pinfunction "2_2") (pintype "passive"))
      (node (ref "R30") (pin "1") (pinfunction "1_1") (pintype "passive"))
    )
    (net (code "45") (name "Net-(JP3-Pad4)") (class "Default")
      (node (ref "JP3") (pin "4") (pinfunction "4_4") (pintype "passive"))
      (node (ref "R31") (pin "1") (pinfunction "1_1") (pintype "passive"))
    )
    (net (code "46") (name "Net-(JP3-Pad5)") (class "Default")
      (node (ref "JP3") (pin "5") (pinfunction "5_5") (pintype "passive"))
      (node (ref "R32") (pin "1") (pinfunction "1_1") (pintype "passive"))
    )
    (net (code "47") (name "Net-(JP3-Pad6)") (class "Default")
      (node (ref "JP3") (pin "6") (pinfunction "6_6") (pintype "passive"))
      (node (ref "R33") (pin "1") (pinfunction "1_1") (pintype "passive"))
    )
    (net (code "48") (name "Net-(JP4-Pad2)") (class "Default")
      (node (ref "JP4") (pin "2") (pinfunction "2_2") (pintype "passive"))
      (node (ref "R18") (pin "2") (pinfunction "2_2") (pintype "passive"))
    )
    (net (code "49") (name "Net-(LED1-PadC)") (class "Default")
      (node (ref "LED1") (pin "C") (pinfunction "C_C") (pintype "passive"))
      (node (ref "R19") (pin "2") (pinfunction "2_2") (pintype "passive"))
    )
    (net (code "50") (name "Net-(LED2-PadC)") (class "Default")
      (node (ref "LED2") (pin "C") (pinfunction "C_C") (pintype "passive"))
      (node (ref "R20") (pin "2") (pinfunction "2_2") (pintype "passive"))
    )
    (net (code "51") (name "Net-(LED3-PadC)") (class "Default")
      (node (ref "LED3") (pin "C") (pinfunction "C_C") (pintype "passive"))
      (node (ref "R21") (pin "2") (pinfunction "2_2") (pintype "passive"))
    )
    (net (code "52") (name "Net-(LED4-PadC)") (class "Default")
      (node (ref "LED4") (pin "C") (pinfunction "C_C") (pintype "passive"))
      (node (ref "R22") (pin "2") (pinfunction "2_2") (pintype "passive"))
    )
    (net (code "53") (name "Net-(LED5-PadC)") (class "Default")
      (node (ref "LED5") (pin "C") (pinfunction "C_C") (pintype "passive"))
      (node (ref "R23") (pin "2") (pinfunction "2_2") (pintype "passive"))
    )
    (net (code "54") (name "Net-(LED6-PadC)") (class "Default")
      (node (ref "LED6") (pin "C") (pinfunction "C_C") (pintype "passive"))
      (node (ref "R24") (pin "2") (pinfunction "2_2") (pintype "passive"))
    )
    (net (code "55") (name "Net-(LED7-PadC)") (class "Default")
      (node (ref "LED7") (pin "C") (pinfunction "C_C") (pintype "passive"))
      (node (ref "R34") (pin "2") (pinfunction "2_2") (pintype "passive"))
    )
    (net (code "56") (name "Net-(LED8-PadC)") (class "Default")
      (node (ref "LED8") (pin "C") (pinfunction "C_C") (pintype "passive"))
      (node (ref "R39") (pin "2") (pinfunction "2_2") (pintype "passive"))
    )
    (net (code "57") (name "Net-(Q1-B)") (class "Default")
      (node (ref "Q1") (pin "1") (pinfunction "B_1") (pintype "passive"))
      (node (ref "R37") (pin "1") (pinfunction "1_1") (pintype "passive"))
    )
    (net (code "58") (name "Net-(U1-PLL)") (class "Default")
      (node (ref "C3") (pin "1") (pinfunction "1_1") (pintype "passive"))
      (node (ref "C4") (pin "1") (pinfunction "1_1") (pintype "passive"))
      (node (ref "U1") (pin "14") (pinfunction "PLL_14") (pintype "bidirectional"))
    )
    (net (code "59") (name "Net-(U3-PLL)") (class "Default")
      (node (ref "C10") (pin "1") (pinfunction "1_1") (pintype "passive"))
      (node (ref "C9") (pin "1") (pinfunction "1_1") (pintype "passive"))
      (node (ref "U3") (pin "14") (pinfunction "PLL_14") (pintype "bidirectional"))
    )
    (net (code "60") (name "Net-(U5-PLL)") (class "Default")
      (node (ref "C15") (pin "1") (pinfunction "1_1") (pintype "passive"))
      (node (ref "C16") (pin "1") (pinfunction "1_1") (pintype "passive"))
      (node (ref "U5") (pin "14") (pinfunction "PLL_14") (pintype "bidirectional"))
    )
    (net (code "61") (name "Net-(U10B-PC14)") (class "Default")
      (node (ref "C46") (pin "2") (pinfunction "2_2") (pintype "passive"))
      (node (ref "U10") (pin "8") (pinfunction "PC14_8") (pintype "bidirectional"))
      (node (ref "Y1") (pin "2") (pinfunction "2_2") (pintype "bidirectional"))
    )
    (net (code "62") (name "Net-(U10B-PC15)") (class "Default")
      (node (ref "C47") (pin "2") (pinfunction "2_2") (pintype "passive"))
      (node (ref "U10") (pin "9") (pinfunction "PC15_9") (pintype "bidirectional"))
      (node (ref "Y1") (pin "1") (pinfunction "1_1") (pintype "bidirectional"))
    )
    (net (code "63") (name "Net-(U10C-PE2)") (class "Default")
      (node (ref "R23") (pin "1") (pinfunction "1_1") (pintype "passive"))
      (node (ref "U10") (pin "1") (pinfunction "PE2_1") (pintype "bidirectional"))
    )
    (net (code "64") (name "Net-(U10C-PE3)") (class "Default")
      (node (ref "R22") (pin "1") (pinfunction "1_1") (pintype "passive"))
      (node (ref "U10") (pin "2") (pinfunction "PE3_2") (pintype "bidirectional"))
    )
    (net (code "65") (name "Net-(U10C-PE4)") (class "Default")
      (node (ref "R21") (pin "1") (pinfunction "1_1") (pintype "passive"))
      (node (ref "U10") (pin "3") (pinfunction "PE4_3") (pintype "bidirectional"))
    )
    (net (code "66") (name "Net-(U10C-PE5)") (class "Default")
      (node (ref "R20") (pin "1") (pinfunction "1_1") (pintype "passive"))
      (node (ref "U10") (pin "4") (pinfunction "PE5_4") (pintype "bidirectional"))
    )
    (net (code "67") (name "Net-(U10C-PE6)") (class "Default")
      (node (ref "R19") (pin "1") (pinfunction "1_1") (pintype "passive"))
      (node (ref "U10") (pin "5") (pinfunction "PE6_5") (pintype "bidirectional"))
    )
    (net (code "68") (name "Net-(U10C-PH0)") (class "Default")
      (node (ref "C49") (pin "2") (pinfunction "2_2") (pintype "passive"))
      (node (ref "U10") (pin "12") (pinfunction "PH0_12") (pintype "bidirectional"))
      (node (ref "Y2") (pin "2") (pinfunction "2_2") (pintype "bidirectional"))
    )
    (net (code "69") (name "Net-(U10C-PH1)") (class "Default")
      (node (ref "C50") (pin "2") (pinfunction "2_2") (pintype "passive"))
      (node (ref "U10") (pin "13") (pinfunction "PH1_13") (pintype "bidirectional"))
      (node (ref "Y2") (pin "1") (pinfunction "1_1") (pintype "bidirectional"))
    )
    (net (code "70") (name "Net-(U10C-VCAP_1)") (class "Default")
      (node (ref "C42") (pin "2") (pinfunction "2_2") (pintype "passive"))
      (node (ref "U10") (pin "49") (pinfunction "VCAP_1_49") (pintype "passive"))
    )
    (net (code "71") (name "Net-(U10C-VCAP_2)") (class "Default")
      (node (ref "C41") (pin "2") (pinfunction "2_2") (pintype "passive"))
      (node (ref "U10") (pin "73") (pinfunction "VCAP_2_73") (pintype "passive"))
    )
    (net (code "72") (name "Net-(U10C-VDDA)") (class "Default")
      (node (ref "C38") (pin "1") (pinfunction "1_1") (pintype "passive"))
      (node (ref "C39") (pin "1") (pinfunction "1_1") (pintype "passive"))
      (node (ref "R13") (pin "1") (pinfunction "1_1") (pintype "passive"))
      (node (ref "U10") (pin "21") (pinfunction "VREF+_21") (pintype "power_in"))
      (node (ref "U10") (pin "22") (pinfunction "VDDA_22") (pintype "power_in"))
    )
    (net (code "73") (name "SPI1_MISO") (class "Default")
      (node (ref "U1") (pin "4") (pinfunction "SDO_4") (pintype "bidirectional"))
      (node (ref "U10") (pin "31") (pinfunction "PA6_31") (pintype "bidirectional"))
      (node (ref "U2") (pin "7") (pinfunction "SA0/SDO_7") (pintype "bidirectional"))
      (node (ref "U3") (pin "4") (pinfunction "SDO_4") (pintype "bidirectional"))
      (node (ref "U4") (pin "7") (pinfunction "SA0/SDO_7") (pintype "bidirectional"))
      (node (ref "U5") (pin "4") (pinfunction "SDO_4") (pintype "bidirectional"))
      (node (ref "U6") (pin "7") (pinfunction "SA0/SDO_7") (pintype "bidirectional"))
    )
    (net (code "74") (name "SPI1_MOSI") (class "Default")
      (node (ref "U1") (pin "3") (pinfunction "SDA/SDI_3") (pintype "bidirectional"))
      (node (ref "U10") (pin "32") (pinfunction "PA7_32") (pintype "bidirectional"))
      (node (ref "U2") (pin "6") (pinfunction "SDA/SDI_6") (pintype "bidirectional"))
      (node (ref "U3") (pin "3") (pinfunction "SDA/SDI_3") (pintype "bidirectional"))
      (node (ref "U4") (pin "6") (pinfunction "SDA/SDI_6") (pintype "bidirectional"))
      (node (ref "U5") (pin "3") (pinfunction "SDA/SDI_3") (pintype "bidirectional"))
      (node (ref "U6") (pin "6") (pinfunction "SDA/SDI_6") (pintype "bidirectional"))
    )
    (net (code "75") (name "SPI1_SCK") (class "Default")
      (node (ref "U1") (pin "2") (pinfunction "SCL_2") (pintype "bidirectional"))
      (node (ref "U10") (pin "30") (pinfunction "PA5_30") (pintype "bidirectional"))
      (node (ref "U2") (pin "4") (pinfunction "SCL/SPC_4") (pintype "bidirectional"))
      (node (ref "U3") (pin "2") (pinfunction "SCL_2") (pintype "bidirectional"))
      (node (ref "U4") (pin "4") (pinfunction "SCL/SPC_4") (pintype "bidirectional"))
      (node (ref "U5") (pin "2") (pinfunction "SCL_2") (pintype "bidirectional"))
      (node (ref "U6") (pin "4") (pinfunction "SCL/SPC_4") (pintype "bidirectional"))
    )
    (net (code "76") (name "SPI3_MISO") (class "Default")
      (node (ref "U10") (pin "90") (pinfunction "PB4_90") (pintype "bidirectional"))
      (node (ref "U7") (pin "P$5") (pinfunction "SDO/ADR_P$5") (pintype "bidirectional"))
      (node (ref "U8") (pin "P$5") (pinfunction "SDO/ADR_P$5") (pintype "bidirectional"))
      (node (ref "U9") (pin "P$5") (pinfunction "SDO/ADR_P$5") (pintype "bidirectional"))
    )
    (net (code "77") (name "SPI3_MOSI") (class "Default")
      (node (ref "U10") (pin "91") (pinfunction "PB5_91") (pintype "bidirectional"))
      (node (ref "U7") (pin "P$3") (pinfunction "SDI/SDA_P$3") (pintype "bidirectional"))
      (node (ref "U8") (pin "P$3") (pinfunction "SDI/SDA_P$3") (pintype "bidirectional"))
      (node (ref "U9") (pin "P$3") (pinfunction "SDI/SDA_P$3") (pintype "bidirectional"))
    )
    (net (code "78") (name "SPI3_SCK{slash}SWO") (class "Default")
      (node (ref "R33") (pin "2") (pinfunction "2_2") (pintype "passive"))
      (node (ref "U10") (pin "89") (pinfunction "PB3_89") (pintype "bidirectional"))
      (node (ref "U7") (pin "P$4") (pinfunction "SCK/SCL_P$4") (pintype "bidirectional"))
      (node (ref "U8") (pin "P$4") (pinfunction "SCK/SCL_P$4") (pintype "bidirectional"))
      (node (ref "U9") (pin "P$4") (pinfunction "SCK/SCL_P$4") (pintype "bidirectional"))
    )
    (net (code "79") (name "SWCLK{slash}PA14") (class "Default")
      (node (ref "R30") (pin "2") (pinfunction "2_2") (pintype "passive"))
      (node (ref "U10") (pin "76") (pinfunction "PA14_76") (pintype "bidirectional"))
    )
    (net (code "80") (name "SWDIO{slash}PA13") (class "Default")
      (node (ref "R31") (pin "2") (pinfunction "2_2") (pintype "passive"))
      (node (ref "U10") (pin "72") (pinfunction "PA13_72") (pintype "bidirectional"))
    )
    (net (code "81") (name "VCC") (class "Default")
      (node (ref "C1") (pin "1") (pinfunction "1_1") (pintype "passive"))
      (node (ref "C11") (pin "1") (pinfunction "1_1") (pintype "passive"))
      (node (ref "C12") (pin "1") (pinfunction "1_1") (pintype "passive"))
      (node (ref "C13") (pin "1") (pinfunction "1_1") (pintype "passive"))
      (node (ref "C14") (pin "1") (pinfunction "1_1") (pintype "passive"))
      (node (ref "C17") (pin "1") (pinfunction "1_1") (pintype "passive"))
      (node (ref "C18") (pin "1") (pinfunction "1_1") (pintype "passive"))
      (node (ref "C19") (pin "1") (pinfunction "1_1") (pintype "passive"))
      (node (ref "C2") (pin "1") (pinfunction "1_1") (pintype "passive"))
      (node (ref "C20") (pin "1") (pinfunction "1_1") (pintype "passive"))
      (node (ref "C21") (pin "1") (pinfunction "1_1") (pintype "passive"))
      (node (ref "C22") (pin "1") (pinfunction "1_1") (pintype "passive"))
      (node (ref "C23") (pin "1") (pinfunction "1_1") (pintype "passive"))
      (node (ref "C24") (pin "1") (pinfunction "1_1") (pintype "passive"))
      (node (ref "C26") (pin "1") (pinfunction "1_1") (pintype "passive"))
      (node (ref "C28") (pin "1") (pinfunction "1_1") (pintype "passive"))
      (node (ref "C29") (pin "1") (pinfunction "1_1") (pintype "passive"))
      (node (ref "C30") (pin "1") (pinfunction "1_1") (pintype "passive"))
      (node (ref "C31") (pin "1") (pinfunction "1_1") (pintype "passive"))
      (node (ref "C32") (pin "1") (pinfunction "1_1") (pintype "passive"))
      (node (ref "C33") (pin "1") (pinfunction "1_1") (pintype "passive"))
      (node (ref "C34") (pin "1") (pinfunction "1_1") (pintype "passive"))
      (node (ref "C35") (pin "1") (pinfunction "1_1") (pintype "passive"))
      (node (ref "C36") (pin "1") (pinfunction "1_1") (pintype "passive"))
      (node (ref "C37") (pin "1") (pinfunction "1_1") (pintype "passive"))
      (node (ref "C40") (pin "2") (pinfunction "2_2") (pintype "passive"))
      (node (ref "C48") (pin "2") (pinfunction "2_2") (pintype "passive"))
      (node (ref "C5") (pin "1") (pinfunction "1_1") (pintype "passive"))
      (node (ref "C6") (pin "1") (pinfunction "1_1") (pintype "passive"))
      (node (ref "C7") (pin "1") (pinfunction "1_1") (pintype "passive"))
      (node (ref "C8") (pin "1") (pinfunction "1_1") (pintype "passive"))
      (node (ref "IC2") (pin "1") (pinfunction "VOUT_1_1") (pintype "bidirectional"))
      (node (ref "IC2") (pin "2") (pinfunction "VOUT_2_2") (pintype "bidirectional"))
      (node (ref "LED1") (pin "A") (pinfunction "A_A") (pintype "passive"))
      (node (ref "LED2") (pin "A") (pinfunction "A_A") (pintype "passive"))
      (node (ref "LED3") (pin "A") (pinfunction "A_A") (pintype "passive"))
      (node (ref "LED4") (pin "A") (pinfunction "A_A") (pintype "passive"))
      (node (ref "LED5") (pin "A") (pinfunction "A_A") (pintype "passive"))
      (node (ref "LED6") (pin "A") (pinfunction "A_A") (pintype "passive"))
      (node (ref "P1") (pin "4") (pinfunction "4_4") (pintype "passive"))
      (node (ref "P2") (pin "4") (pinfunction "4_4") (pintype "passive"))
      (node (ref "R10") (pin "2") (pinfunction "2_2") (pintype "passive"))
      (node (ref "R11") (pin "2") (pinfunction "2_2") (pintype "passive"))
      (node (ref "R12") (pin "2") (pinfunction "2_2") (pintype "passive"))
      (node (ref "R13") (pin "2") (pinfunction "2_2") (pintype "passive"))
      (node (ref "R14") (pin "2") (pinfunction "2_2") (pintype "passive"))
      (node (ref "R15") (pin "2") (pinfunction "2_2") (pintype "passive"))
      (node (ref "R17") (pin "2") (pinfunction "2_2") (pintype "passive"))
      (node (ref "R2") (pin "2") (pinfunction "2_2") (pintype "passive"))
      (node (ref "R25") (pin "2") (pinfunction "2_2") (pintype "passive"))
      (node (ref "R26") (pin "2") (pinfunction "2_2") (pintype "passive"))
      (node (ref "R28") (pin "1") (pinfunction "1_1") (pintype "passive"))
      (node (ref "R35") (pin "2") (pinfunction "2_2") (pintype "passive"))
      (node (ref "R36") (pin "2") (pinfunction "2_2") (pintype "passive"))
      (node (ref "R38") (pin "2") (pinfunction "2_2") (pintype "passive"))
      (node (ref "R4") (pin "2") (pinfunction "2_2") (pintype "passive"))
      (node (ref "R5") (pin "2") (pinfunction "2_2") (pintype "passive"))
      (node (ref "R7") (pin "2") (pinfunction "2_2") (pintype "passive"))
      (node (ref "R8") (pin "2") (pinfunction "2_2") (pintype "passive"))
      (node (ref "R9") (pin "2") (pinfunction "2_2") (pintype "passive"))
      (node (ref "S2") (pin "1") (pinfunction "1_1") (pintype "bidirectional"))
      (node (ref "S2") (pin "2") (pinfunction "2_2") (pintype "bidirectional"))
      (node (ref "U1") (pin "1") (pinfunction "VDDIO_1") (pintype "bidirectional"))
      (node (ref "U1") (pin "15") (pinfunction "RSVDV_15") (pintype "bidirectional"))
      (node (ref "U1") (pin "16") (pinfunction "VDD_16") (pintype "bidirectional"))
      (node (ref "U10") (pin "100") (pinfunction "VDD_100") (pintype "power_in"))
      (node (ref "U10") (pin "11") (pinfunction "VDD_11") (pintype "power_in"))
      (node (ref "U10") (pin "19") (pinfunction "VDD_19") (pintype "power_in"))
      (node (ref "U10") (pin "28") (pinfunction "VDD_28") (pintype "power_in"))
      (node (ref "U10") (pin "50") (pinfunction "VDD_50") (pintype "power_in"))
      (node (ref "U10") (pin "6") (pinfunction "VBAT_6") (pintype "power_in"))
      (node (ref "U10") (pin "75") (pinfunction "VDD_75") (pintype "power_in"))
      (node (ref "U2") (pin "1") (pinfunction "VDDIO_1") (pintype "bidirectional"))
      (node (ref "U2") (pin "14") (pinfunction "VDD_14") (pintype "bidirectional"))
      (node (ref "U3") (pin "1") (pinfunction "VDDIO_1") (pintype "bidirectional"))
      (node (ref "U3") (pin "15") (pinfunction "RSVDV_15") (pintype "bidirectional"))
      (node (ref "U3") (pin "16") (pinfunction "VDD_16") (pintype "bidirectional"))
      (node (ref "U4") (pin "1") (pinfunction "VDDIO_1") (pintype "bidirectional"))
      (node (ref "U4") (pin "14") (pinfunction "VDD_14") (pintype "bidirectional"))
      (node (ref "U5") (pin "1") (pinfunction "VDDIO_1") (pintype "bidirectional"))
      (node (ref "U5") (pin "15") (pinfunction "RSVDV_15") (pintype "bidirectional"))
      (node (ref "U5") (pin "16") (pinfunction "VDD_16") (pintype "bidirectional"))
      (node (ref "U6") (pin "1") (pinfunction "VDDIO_1") (pintype "bidirectional"))
      (node (ref "U6") (pin "14") (pinfunction "VDD_14") (pintype "bidirectional"))
      (node (ref "U7") (pin "P$6") (pinfunction "VDDIO_P$6") (pintype "bidirectional"))
      (node (ref "U7") (pin "P$8") (pinfunction "VDD_P$8") (pintype "bidirectional"))
      (node (ref "U8") (pin "P$6") (pinfunction "VDDIO_P$6") (pintype "bidirectional"))
      (node (ref "U8") (pin "P$8") (pinfunction "VDD_P$8") (pintype "bidirectional"))
      (node (ref "U9") (pin "P$6") (pinfunction "VDDIO_P$6") (pintype "bidirectional"))
      (node (ref "U9") (pin "P$8") (pinfunction "VDD_P$8") (pintype "bidirectional"))
    )
    (net (code "82") (name "unconnected-(IC2-NC-Pad5)") (class "Default")
      (node (ref "IC2") (pin "5") (pinfunction "NC_5") (pintype "no_connect"))
    )
    (net (code "83") (name "unconnected-(J1-ID-Pad4)") (class "Default")
      (node (ref "J1") (pin "4") (pinfunction "ID_4") (pintype "bidirectional"))
    )
    (net (code "84") (name "unconnected-(U$2-Pad2)") (class "Default")
      (node (ref "U$2") (pin "2") (pinfunction "2_2") (pintype "bidirectional"))
    )
    (net (code "85") (name "unconnected-(U$3-Pad2)") (class "Default")
      (node (ref "U$3") (pin "2") (pinfunction "2_2") (pintype "bidirectional"))
    )
    (net (code "86") (name "unconnected-(U1-INT1-Pad7)") (class "Default")
      (node (ref "U1") (pin "7") (pinfunction "INT1_7") (pintype "bidirectional"))
    )
    (net (code "87") (name "unconnected-(U1-INT2-Pad6)") (class "Default")
      (node (ref "U1") (pin "6") (pinfunction "INT2_6") (pintype "bidirectional"))
    )
    (net (code "88") (name "unconnected-(U2-INT1-Pad11)") (class "Default")
      (node (ref "U2") (pin "11") (pinfunction "INT1_11") (pintype "bidirectional"))
    )
    (net (code "89") (name "unconnected-(U2-INT2-Pad9)") (class "Default")
      (node (ref "U2") (pin "9") (pinfunction "INT2_9") (pintype "bidirectional"))
    )
    (net (code "90") (name "unconnected-(U3-INT1-Pad7)") (class "Default")
      (node (ref "U3") (pin "7") (pinfunction "INT1_7") (pintype "bidirectional"))
    )
    (net (code "91") (name "unconnected-(U3-INT2-Pad6)") (class "Default")
      (node (ref "U3") (pin "6") (pinfunction "INT2_6") (pintype "bidirectional"))
    )
    (net (code "92") (name "unconnected-(U4-INT1-Pad11)") (class "Default")
      (node (ref "U4") (pin "11") (pinfunction "INT1_11") (pintype "bidirectional"))
    )
    (net (code "93") (name "unconnected-(U4-INT2-Pad9)") (class "Default")
      (node (ref "U4") (pin "9") (pinfunction "INT2_9") (pintype "bidirectional"))
    )
    (net (code "94") (name "unconnected-(U5-INT1-Pad7)") (class "Default")
      (node (ref "U5") (pin "7") (pinfunction "INT1_7") (pintype "bidirectional"))
    )
    (net (code "95") (name "unconnected-(U5-INT2-Pad6)") (class "Default")
      (node (ref "U5") (pin "6") (pinfunction "INT2_6") (pintype "bidirectional"))
    )
    (net (code "96") (name "unconnected-(U6-INT1-Pad11)") (class "Default")
      (node (ref "U6") (pin "11") (pinfunction "INT1_11") (pintype "bidirectional"))
    )
    (net (code "97") (name "unconnected-(U6-INT2-Pad9)") (class "Default")
      (node (ref "U6") (pin "9") (pinfunction "INT2_9") (pintype "bidirectional"))
    )
    (net (code "98") (name "unconnected-(U10A-PA1-Pad24)") (class "Default")
      (node (ref "U10") (pin "24") (pinfunction "PA1_24") (pintype "bidirectional"))
    )
    (net (code "99") (name "unconnected-(U10A-PA4-Pad29)") (class "Default")
      (node (ref "U10") (pin "29") (pinfunction "PA4_29") (pintype "bidirectional"))
    )
    (net (code "100") (name "unconnected-(U10A-PA8-Pad67)") (class "Default")
      (node (ref "U10") (pin "67") (pinfunction "PA8_67") (pintype "bidirectional"))
    )
    (net (code "101") (name "unconnected-(U10A-PB0-Pad35)") (class "Default")
      (node (ref "U10") (pin "35") (pinfunction "PB0_35") (pintype "bidirectional"))
    )
    (net (code "102") (name "unconnected-(U10A-PB1-Pad36)") (class "Default")
      (node (ref "U10") (pin "36") (pinfunction "PB1_36") (pintype "bidirectional"))
    )
    (net (code "103") (name "unconnected-(U10A-PB8-Pad95)") (class "Default")
      (node (ref "U10") (pin "95") (pinfunction "PB8_95") (pintype "bidirectional"))
    )
    (net (code "104") (name "unconnected-(U10A-PB9-Pad96)") (class "Default")
      (node (ref "U10") (pin "96") (pinfunction "PB9_96") (pintype "bidirectional"))
    )
    (net (code "105") (name "unconnected-(U10B-PC0-Pad15)") (class "Default")
      (node (ref "U10") (pin "15") (pinfunction "PC0_15") (pintype "bidirectional"))
    )
    (net (code "106") (name "unconnected-(U10B-PC10-Pad78)") (class "Default")
      (node (ref "U10") (pin "78") (pinfunction "PC10_78") (pintype "bidirectional"))
    )
    (net (code "107") (name "unconnected-(U10B-PC11-Pad79)") (class "Default")
      (node (ref "U10") (pin "79") (pinfunction "PC11_79") (pintype "bidirectional"))
    )
    (net (code "108") (name "unconnected-(U10B-PC12-Pad80)") (class "Default")
      (node (ref "U10") (pin "80") (pinfunction "PC12_80") (pintype "bidirectional"))
    )
    (net (code "109") (name "unconnected-(U10B-PC13-Pad7)") (class "Default")
      (node (ref "U10") (pin "7") (pinfunction "PC13_7") (pintype "bidirectional"))
    )
    (net (code "110") (name "unconnected-(U10B-PD0-Pad81)") (class "Default")
      (node (ref "U10") (pin "81") (pinfunction "PD0_81") (pintype "bidirectional"))
    )
    (net (code "111") (name "unconnected-(U10B-PD1-Pad82)") (class "Default")
      (node (ref "U10") (pin "82") (pinfunction "PD1_82") (pintype "bidirectional"))
    )
    (net (code "112") (name "unconnected-(U10B-PD2-Pad83)") (class "Default")
      (node (ref "U10") (pin "83") (pinfunction "PD2_83") (pintype "bidirectional"))
    )
    (net (code "113") (name "unconnected-(U10B-PD3-Pad84)") (class "Default")
      (node (ref "U10") (pin "84") (pinfunction "PD3_84") (pintype "bidirectional"))
    )
    (net (code "114") (name "unconnected-(U10B-PD4-Pad85)") (class "Default")
      (node (ref "U10") (pin "85") (pinfunction "PD4_85") (pintype "bidirectional"))
    )
    (net (code "115") (name "unconnected-(U10B-PD5-Pad86)") (class "Default")
      (node (ref "U10") (pin "86") (pinfunction "PD5_86") (pintype "bidirectional"))
    )
    (net (code "116") (name "unconnected-(U10B-PD6-Pad87)") (class "Default")
      (node (ref "U10") (pin "87") (pinfunction "PD6_87") (pintype "bidirectional"))
    )
    (net (code "117") (name "unconnected-(U10B-PD7-Pad88)") (class "Default")
      (node (ref "U10") (pin "88") (pinfunction "PD7_88") (pintype "bidirectional"))
    )
    (net (code "118") (name "unconnected-(U10B-PD8-Pad55)") (class "Default")
      (node (ref "U10") (pin "55") (pinfunction "PD8_55") (pintype "bidirectional"))
    )
    (net (code "119") (name "unconnected-(U10B-PD9-Pad56)") (class "Default")
      (node (ref "U10") (pin "56") (pinfunction "PD9_56") (pintype "bidirectional"))
    )
    (net (code "120") (name "unconnected-(U10B-PD10-Pad57)") (class "Default")
      (node (ref "U10") (pin "57") (pinfunction "PD10_57") (pintype "bidirectional"))
    )
    (net (code "121") (name "unconnected-(U10B-PD11-Pad58)") (class "Default")
      (node (ref "U10") (pin "58") (pinfunction "PD11_58") (pintype "bidirectional"))
    )
    (net (code "122") (name "unconnected-(U10B-PD12-Pad59)") (class "Default")
      (node (ref "U10") (pin "59") (pinfunction "PD12_59") (pintype "bidirectional"))
    )
    (net (code "123") (name "unconnected-(U10B-PD13-Pad60)") (class "Default")
      (node (ref "U10") (pin "60") (pinfunction "PD13_60") (pintype "bidirectional"))
    )
    (net (code "124") (name "unconnected-(U10B-PD14-Pad61)") (class "Default")
      (node (ref "U10") (pin "61") (pinfunction "PD14_61") (pintype "bidirectional"))
    )
    (net (code "125") (name "unconnected-(U10B-PD15-Pad62)") (class "Default")
      (node (ref "U10") (pin "62") (pinfunction "PD15_62") (pintype "bidirectional"))
    )
    (net (code "126") (name "unconnected-(U10C-PE0-Pad97)") (class "Default")
      (node (ref "U10") (pin "97") (pinfunction "PE0_97") (pintype "bidirectional"))
    )
    (net (code "127") (name "unconnected-(U10C-PE1-Pad98)") (class "Default")
      (node (ref "U10") (pin "98") (pinfunction "PE1_98") (pintype "bidirectional"))
    )
    (net (code "128") (name "unconnected-(U10C-PE7-Pad38)") (class "Default")
      (node (ref "U10") (pin "38") (pinfunction "PE7_38") (pintype "bidirectional"))
    )
    (net (code "129") (name "unconnected-(U10C-PE8-Pad39)") (class "Default")
      (node (ref "U10") (pin "39") (pinfunction "PE8_39") (pintype "bidirectional"))
    )
    (net (code "130") (name "unconnected-(U10C-PE12-Pad43)") (class "Default")
      (node (ref "U10") (pin "43") (pinfunction "PE12_43") (pintype "bidirectional"))
    )
    (net (code "131") (name "unconnected-(U10C-PE13-Pad44)") (class "Default")
      (node (ref "U10") (pin "44") (pinfunction "PE13_44") (pintype "bidirectional"))
    )
    (net (code "132") (name "unconnected-(U10C-PE14-Pad45)") (class "Default")
      (node (ref "U10") (pin "45") (pinfunction "PE14_45") (pintype "bidirectional"))
    )
    (net (code "133") (name "unconnected-(U10C-PE15-Pad46)") (class "Default")
      (node (ref "U10") (pin "46") (pinfunction "PE15_46") (pintype "bidirectional"))
    )
  )
)
